# CAN.net
KiCad netlist of a schematic drawn in Altium Designer
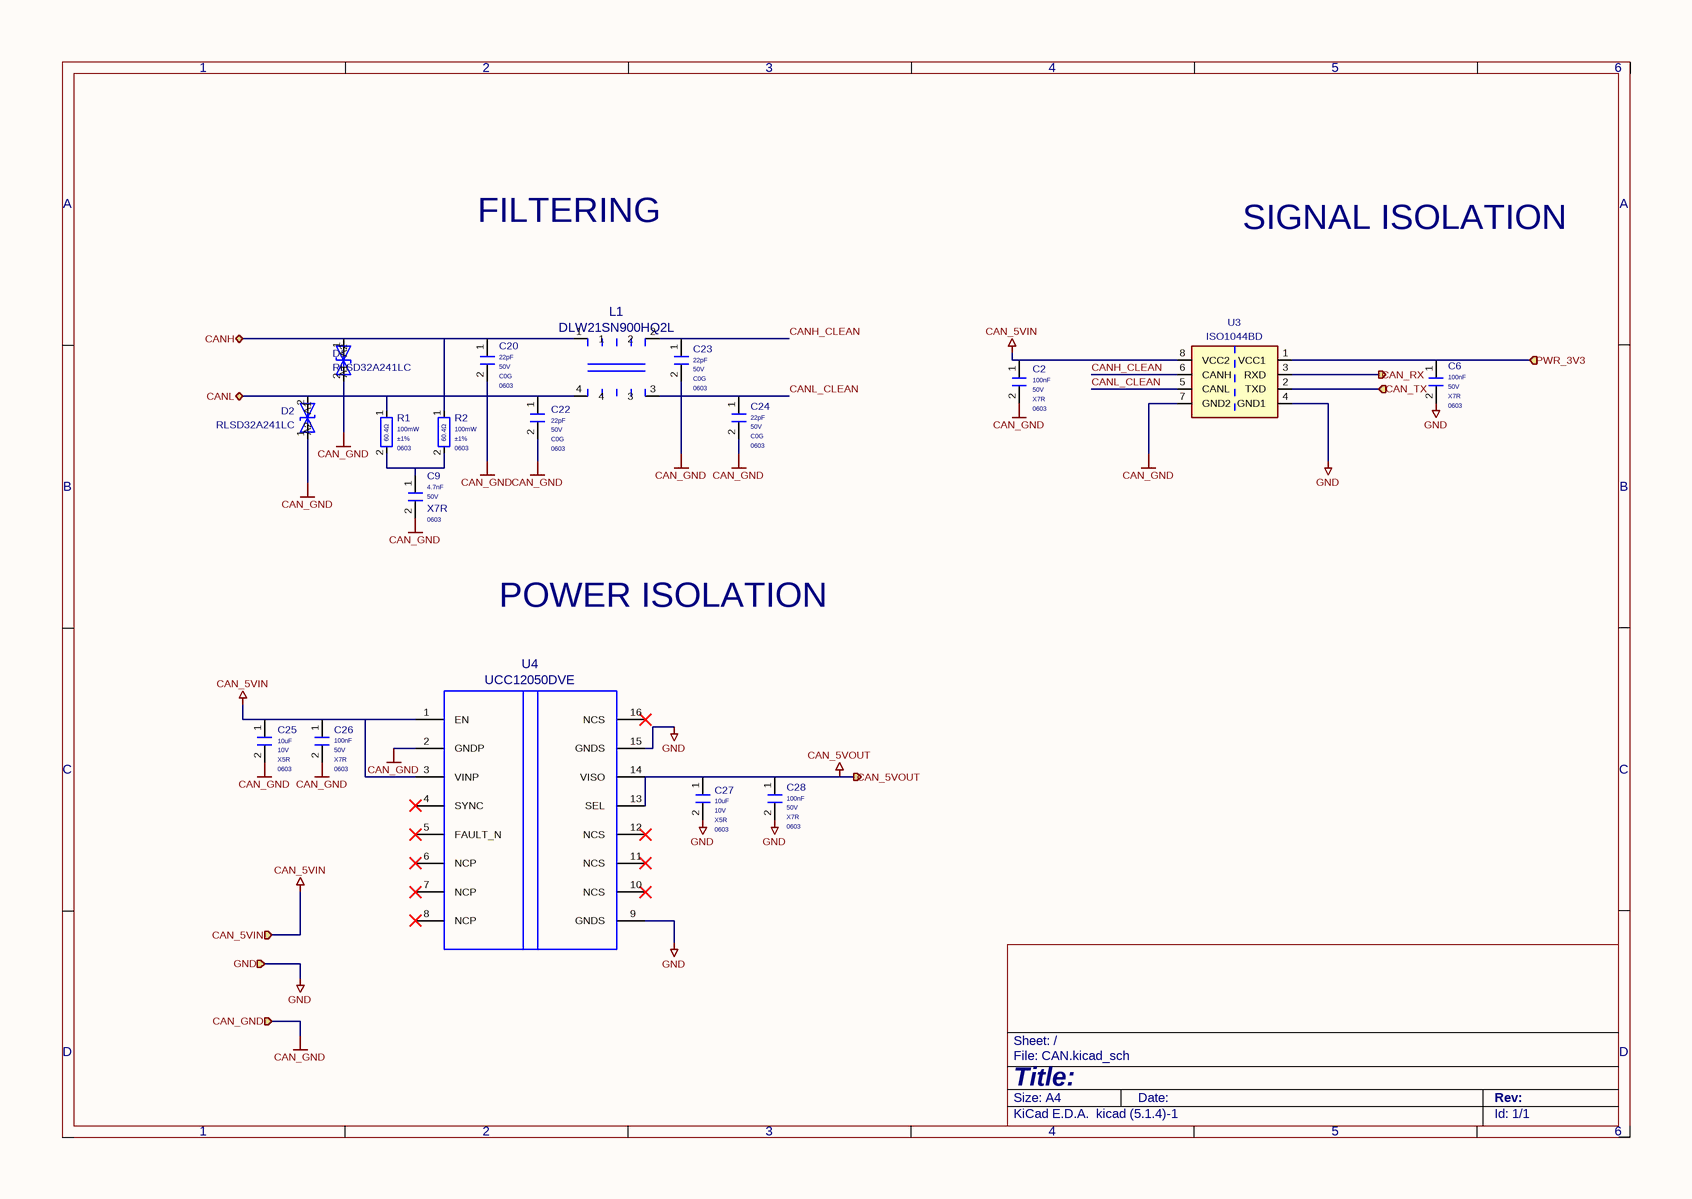
[diagram p0: CAN.SchDoc]

(export (version "E")
  (design (tool "Eeschema 10.0.6"))
  (components
    (comp (ref "C2")
      (value "100nF")
      (description "50V 100nF X7R ±10% 0603 Multilayer Ceramic Capacitors MLCC - SMD/SMT ROHS")
      (fields
        (field (name "MANUFACTURER") "YAGEO")
        (field (name "PART") "CC0603KRX7R9BB104")
        (field (name "VOLTAGE RATED") "50V")
        (field (name "TEMPERATURE COEFFICIENT") "X7R")
        (field (name "PACKAGE") "0603")
      )
      (libsource (lib "PCM_JLCPCB-Capacitors") (part "0603,100nF"))
    )
    (comp (ref "C6")
      (value "100nF")
      (description "50V 100nF X7R ±10% 0603 Multilayer Ceramic Capacitors MLCC - SMD/SMT ROHS")
      (fields
        (field (name "MANUFACTURER") "YAGEO")
        (field (name "PART") "CC0603KRX7R9BB104")
        (field (name "VOLTAGE RATED") "50V")
        (field (name "TEMPERATURE COEFFICIENT") "X7R")
        (field (name "PACKAGE") "0603")
      )
      (libsource (lib "PCM_JLCPCB-Capacitors") (part "0603,100nF"))
    )
    (comp (ref "C9")
      (value "4.7nF")
      (description "50V 4.7nF X7R ±10% 0603 Multilayer Ceramic Capacitors MLCC - SMD/SMT ROHS")
      (fields
        (field (name "MANUFACTURER") "FH(Guangdong Fenghua Advanced Tech)")
        (field (name "PART") "0603B472K500NT")
        (field (name "VOLTAGE RATED") "50V")
        (field (name "TEMPERATURE COEFFICIENT") "X7R")
        (field (name "PACKAGE") "0603")
      )
      (libsource (lib "PCM_JLCPCB-Capacitors") (part "0603,4.7nF"))
    )
    (comp (ref "C20")
      (value "22pF")
      (description "50V 22pF C0G ±5% 0603 Multilayer Ceramic Capacitors MLCC - SMD/SMT ROHS")
      (fields
        (field (name "MANUFACTURER") "Samsung Electro-Mechanics")
        (field (name "PART") "CL10C220JB8NNNC")
        (field (name "VOLTAGE RATED") "50V")
        (field (name "TEMPERATURE COEFFICIENT") "C0G")
        (field (name "PACKAGE") "0603")
      )
      (libsource (lib "PCM_JLCPCB-Capacitors") (part "0603,22pF"))
    )
    (comp (ref "C22")
      (value "22pF")
      (description "50V 22pF C0G ±5% 0603 Multilayer Ceramic Capacitors MLCC - SMD/SMT ROHS")
      (fields
        (field (name "MANUFACTURER") "Samsung Electro-Mechanics")
        (field (name "PART") "CL10C220JB8NNNC")
        (field (name "VOLTAGE RATED") "50V")
        (field (name "TEMPERATURE COEFFICIENT") "C0G")
        (field (name "PACKAGE") "0603")
      )
      (libsource (lib "PCM_JLCPCB-Capacitors") (part "0603,22pF"))
    )
    (comp (ref "C23")
      (value "22pF")
      (description "50V 22pF C0G ±5% 0603 Multilayer Ceramic Capacitors MLCC - SMD/SMT ROHS")
      (fields
        (field (name "MANUFACTURER") "Samsung Electro-Mechanics")
        (field (name "PART") "CL10C220JB8NNNC")
        (field (name "VOLTAGE RATED") "50V")
        (field (name "TEMPERATURE COEFFICIENT") "C0G")
        (field (name "PACKAGE") "0603")
      )
      (libsource (lib "PCM_JLCPCB-Capacitors") (part "0603,22pF"))
    )
    (comp (ref "C24")
      (value "22pF")
      (description "50V 22pF C0G ±5% 0603 Multilayer Ceramic Capacitors MLCC - SMD/SMT ROHS")
      (fields
        (field (name "MANUFACTURER") "Samsung Electro-Mechanics")
        (field (name "PART") "CL10C220JB8NNNC")
        (field (name "VOLTAGE RATED") "50V")
        (field (name "TEMPERATURE COEFFICIENT") "C0G")
        (field (name "PACKAGE") "0603")
      )
      (libsource (lib "PCM_JLCPCB-Capacitors") (part "0603,22pF"))
    )
    (comp (ref "C25")
      (value "10uF")
      (description "10V 10uF X5R ±10% 0603 Multilayer Ceramic Capacitors MLCC - SMD/SMT ROHS")
      (fields
        (field (name "MANUFACTURER") "Samsung Electro-Mechanics")
        (field (name "PART") "CL10A106KP8NNNC")
        (field (name "VOLTAGE RATED") "10V")
        (field (name "TEMPERATURE COEFFICIENT") "X5R")
        (field (name "PACKAGE") "0603")
      )
      (libsource (lib "PCM_JLCPCB-Capacitors") (part "0603,10uF"))
    )
    (comp (ref "C26")
      (value "100nF")
      (description "50V 100nF X7R ±10% 0603 Multilayer Ceramic Capacitors MLCC - SMD/SMT ROHS")
      (fields
        (field (name "MANUFACTURER") "YAGEO")
        (field (name "PART") "CC0603KRX7R9BB104")
        (field (name "VOLTAGE RATED") "50V")
        (field (name "TEMPERATURE COEFFICIENT") "X7R")
        (field (name "PACKAGE") "0603")
      )
      (libsource (lib "PCM_JLCPCB-Capacitors") (part "0603,100nF"))
    )
    (comp (ref "C27")
      (value "10uF")
      (description "10V 10uF X5R ±10% 0603 Multilayer Ceramic Capacitors MLCC - SMD/SMT ROHS")
      (fields
        (field (name "MANUFACTURER") "Samsung Electro-Mechanics")
        (field (name "PART") "CL10A106KP8NNNC")
        (field (name "VOLTAGE RATED") "10V")
        (field (name "TEMPERATURE COEFFICIENT") "X5R")
        (field (name "PACKAGE") "0603")
      )
      (libsource (lib "PCM_JLCPCB-Capacitors") (part "0603,10uF"))
    )
    (comp (ref "C28")
      (value "100nF")
      (description "50V 100nF X7R ±10% 0603 Multilayer Ceramic Capacitors MLCC - SMD/SMT ROHS")
      (fields
        (field (name "MANUFACTURER") "YAGEO")
        (field (name "PART") "CC0603KRX7R9BB104")
        (field (name "VOLTAGE RATED") "50V")
        (field (name "TEMPERATURE COEFFICIENT") "X7R")
        (field (name "PACKAGE") "0603")
      )
      (libsource (lib "PCM_JLCPCB-Capacitors") (part "0603,100nF"))
    )
    (comp (ref "D1")
      (value "RLSD32A241LC")
      (description "Bidirectional transient-voltage-suppression diode")
      (libsource (lib "Device") (part "D_TVS"))
    )
    (comp (ref "D2")
      (value "RLSD32A241LC")
      (description "Bidirectional transient-voltage-suppression diode")
      (libsource (lib "Device") (part "D_TVS"))
    )
    (comp (ref "L1") (value "DLW21SN900HQ2L") (libsource (lib "2026-03-14_22-01-45") (part "DLW21SN900HQ2L")))
    (comp (ref "R1")
      (value "60.4Ω")
      (description "100mW Thick Film Resistors 75V ±1% ±200ppm/°C 56Ω 0603 Chip Resistor - Surface Mount ROHS")
      (fields
        (field (name "MANUFACTURER") "UNI-ROYAL(Uniroyal Elec)")
        (field (name "PART") "0603WAF560JT5E")
        (field (name "POWER(WATTS)") "100mW")
        (field (name "TOLERANCE") "±1%")
        (field (name "PACKAGE") "0603")
      )
      (libsource (lib "PCM_JLCPCB-Resistors") (part "0603,56Ω"))
    )
    (comp (ref "R2")
      (value "60.4Ω")
      (description "100mW Thick Film Resistors 75V ±1% ±200ppm/°C 56Ω 0603 Chip Resistor - Surface Mount ROHS")
      (fields
        (field (name "MANUFACTURER") "UNI-ROYAL(Uniroyal Elec)")
        (field (name "PART") "0603WAF560JT5E")
        (field (name "POWER(WATTS)") "100mW")
        (field (name "TOLERANCE") "±1%")
        (field (name "PACKAGE") "0603")
      )
      (libsource (lib "PCM_JLCPCB-Resistors") (part "0603,56Ω"))
    )
    (comp (ref "U3")
      (value "ISO1044BD")
      (description "Isolated CAN FD Transceiver, SOIC-8")
      (libsource (lib "Interface_CAN_LIN") (part "ISO1044BD"))
    )
    (comp (ref "U4") (value "UCC12050DVE") (libsource (lib "2026-03-14_23-02-57") (part "UCC12050DVE")))
  )
  (nets
    (net (code "1") (name "/CANH") (class "Default")
      (node (ref "C20") (pin "1") (pinfunction "1_1") (pintype "passive"))
      (node (ref "D1") (pin "1") (pinfunction "A1_1") (pintype "passive"))
      (node (ref "L1") (pin "1") (pinfunction "1_1") (pintype "passive"))
      (node (ref "R2") (pin "1") (pinfunction "1_1") (pintype "passive"))
    )
    (net (code "2") (name "/CANH_CLEAN") (class "Default")
      (node (ref "C23") (pin "1") (pinfunction "1_1") (pintype "passive"))
      (node (ref "L1") (pin "2") (pinfunction "2_2") (pintype "passive"))
      (node (ref "U3") (pin "6") (pinfunction "CANH_6") (pintype "passive"))
    )
    (net (code "3") (name "/CANL") (class "Default")
      (node (ref "C22") (pin "1") (pinfunction "1_1") (pintype "passive"))
      (node (ref "D2") (pin "2") (pinfunction "A2_2") (pintype "passive"))
      (node (ref "L1") (pin "4") (pinfunction "4_4") (pintype "passive"))
      (node (ref "R1") (pin "1") (pinfunction "1_1") (pintype "passive"))
    )
    (net (code "4") (name "/CANL_CLEAN") (class "Default")
      (node (ref "C24") (pin "1") (pinfunction "1_1") (pintype "passive"))
      (node (ref "L1") (pin "3") (pinfunction "3_3") (pintype "passive"))
      (node (ref "U3") (pin "5") (pinfunction "CANL_5") (pintype "passive"))
    )
    (net (code "5") (name "/CAN_RX") (class "Default")
      (node (ref "U3") (pin "3") (pinfunction "RXD_3") (pintype "passive"))
    )
    (net (code "6") (name "/CAN_TX") (class "Default")
      (node (ref "U3") (pin "2") (pinfunction "TXD_2") (pintype "passive"))
    )
    (net (code "7") (name "/PWR_3V3") (class "Default")
      (node (ref "C6") (pin "1") (pinfunction "1_1") (pintype "passive"))
      (node (ref "U3") (pin "1") (pinfunction "VCC1_1") (pintype "passive"))
    )
    (net (code "8") (name "CAN_5VIN") (class "Default")
      (node (ref "C2") (pin "1") (pinfunction "1_1") (pintype "passive"))
      (node (ref "C25") (pin "1") (pinfunction "1_1") (pintype "passive"))
      (node (ref "C26") (pin "1") (pinfunction "1_1") (pintype "passive"))
      (node (ref "U3") (pin "8") (pinfunction "VCC2_8") (pintype "passive"))
      (node (ref "U4") (pin "1") (pinfunction "EN_1") (pintype "passive"))
      (node (ref "U4") (pin "3") (pinfunction "VINP_3") (pintype "passive"))
    )
    (net (code "9") (name "CAN_5VOUT") (class "Default")
      (node (ref "C27") (pin "1") (pinfunction "1_1") (pintype "passive"))
      (node (ref "C28") (pin "1") (pinfunction "1_1") (pintype "passive"))
      (node (ref "U4") (pin "13") (pinfunction "SEL_13") (pintype "passive"))
      (node (ref "U4") (pin "14") (pinfunction "VISO_14") (pintype "passive"))
    )
    (net (code "10") (name "CAN_GND") (class "Default")
      (node (ref "C2") (pin "2") (pinfunction "2_2") (pintype "passive"))
      (node (ref "C20") (pin "2") (pinfunction "2_2") (pintype "passive"))
      (node (ref "C22") (pin "2") (pinfunction "2_2") (pintype "passive"))
      (node (ref "C23") (pin "2") (pinfunction "2_2") (pintype "passive"))
      (node (ref "C24") (pin "2") (pinfunction "2_2") (pintype "passive"))
      (node (ref "C25") (pin "2") (pinfunction "2_2") (pintype "passive"))
      (node (ref "C26") (pin "2") (pinfunction "2_2") (pintype "passive"))
      (node (ref "C9") (pin "2") (pinfunction "2_2") (pintype "passive"))
      (node (ref "D1") (pin "2") (pinfunction "A2_2") (pintype "passive"))
      (node (ref "D2") (pin "1") (pinfunction "A1_1") (pintype "passive"))
      (node (ref "U3") (pin "7") (pinfunction "GND2_7") (pintype "passive"))
      (node (ref "U4") (pin "2") (pinfunction "GNDP_2") (pintype "passive"))
    )
    (net (code "11") (name "GND") (class "Default")
      (node (ref "C27") (pin "2") (pinfunction "2_2") (pintype "passive"))
      (node (ref "C28") (pin "2") (pinfunction "2_2") (pintype "passive"))
      (node (ref "C6") (pin "2") (pinfunction "2_2") (pintype "passive"))
      (node (ref "U3") (pin "4") (pinfunction "GND1_4") (pintype "passive"))
      (node (ref "U4") (pin "15") (pinfunction "GNDS_15") (pintype "passive"))
      (node (ref "U4") (pin "9") (pinfunction "GNDS_9") (pintype "passive"))
    )
    (net (code "12") (name "Net-(C9-Pad1)") (class "Default")
      (node (ref "C9") (pin "1") (pinfunction "1_1") (pintype "passive"))
      (node (ref "R1") (pin "2") (pinfunction "2_2") (pintype "passive"))
      (node (ref "R2") (pin "2") (pinfunction "2_2") (pintype "passive"))
    )
    (net (code "13") (name "unconnected-(U4-FAULT_N-Pad5)") (class "Default")
      (node (ref "U4") (pin "5") (pinfunction "FAULT_N_5") (pintype "passive+no_connect"))
    )
    (net (code "14") (name "unconnected-(U4-NCP-Pad6)") (class "Default")
      (node (ref "U4") (pin "6") (pinfunction "NCP_6") (pintype "passive+no_connect"))
    )
    (net (code "15") (name "unconnected-(U4-NCP-Pad7)") (class "Default")
      (node (ref "U4") (pin "7") (pinfunction "NCP_7") (pintype "passive+no_connect"))
    )
    (net (code "16") (name "unconnected-(U4-NCP-Pad8)") (class "Default")
      (node (ref "U4") (pin "8") (pinfunction "NCP_8") (pintype "passive+no_connect"))
    )
    (net (code "17") (name "unconnected-(U4-NCS-Pad10)") (class "Default")
      (node (ref "U4") (pin "10") (pinfunction "NCS_10") (pintype "passive+no_connect"))
    )
    (net (code "18") (name "unconnected-(U4-NCS-Pad11)") (class "Default")
      (node (ref "U4") (pin "11") (pinfunction "NCS_11") (pintype "passive+no_connect"))
    )
    (net (code "19") (name "unconnected-(U4-NCS-Pad12)") (class "Default")
      (node (ref "U4") (pin "12") (pinfunction "NCS_12") (pintype "passive+no_connect"))
    )
    (net (code "20") (name "unconnected-(U4-NCS-Pad16)") (class "Default")
      (node (ref "U4") (pin "16") (pinfunction "NCS_16") (pintype "passive+no_connect"))
    )
    (net (code "21") (name "unconnected-(U4-SYNC-Pad4)") (class "Default")
      (node (ref "U4") (pin "4") (pinfunction "SYNC_4") (pintype "passive+no_connect"))
    )
  )
)
